# MIPI_To_HDMI.net
KiCad netlist of a schematic drawn in Altium Designer
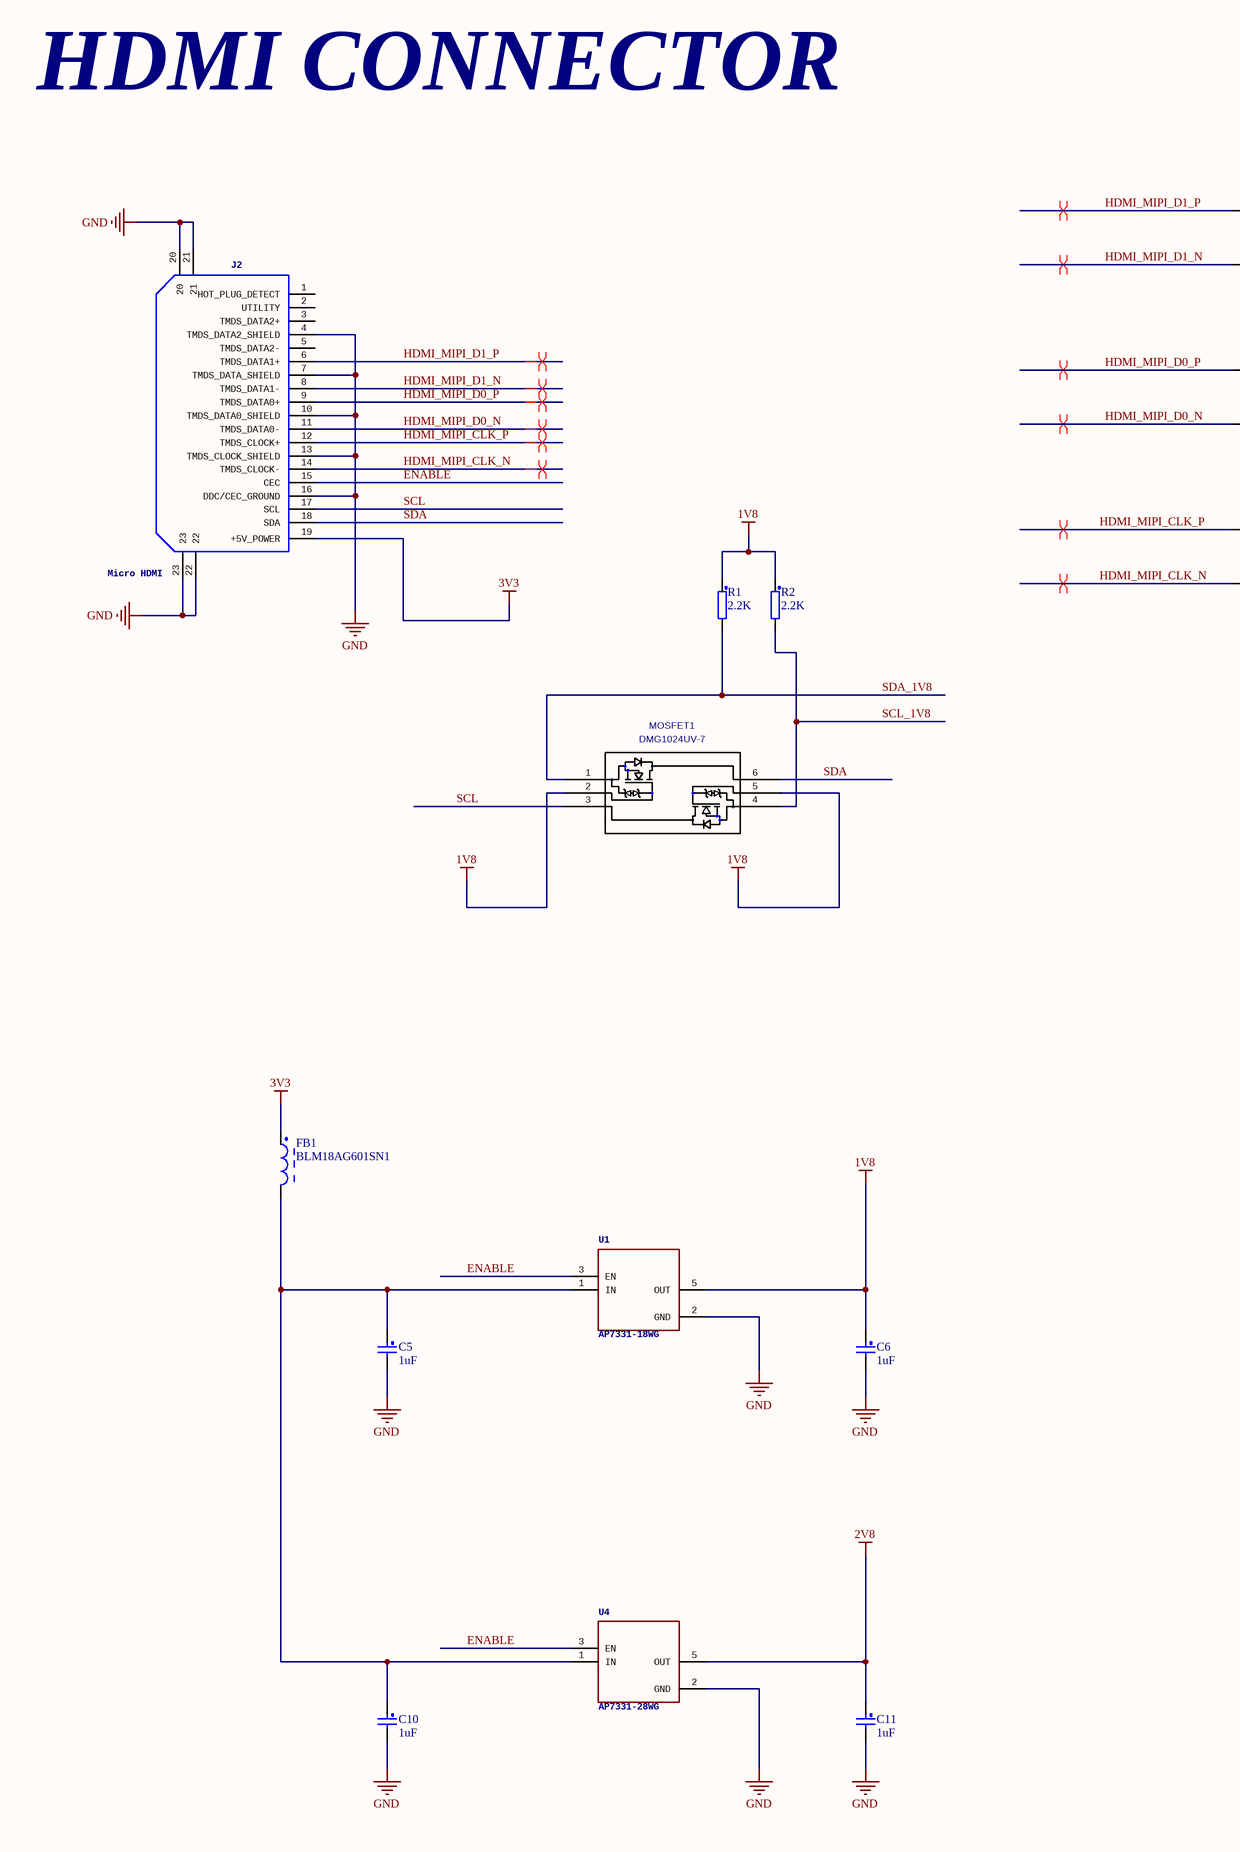
[diagram p0: MIPI_To_HDMI.SchDoc, left]
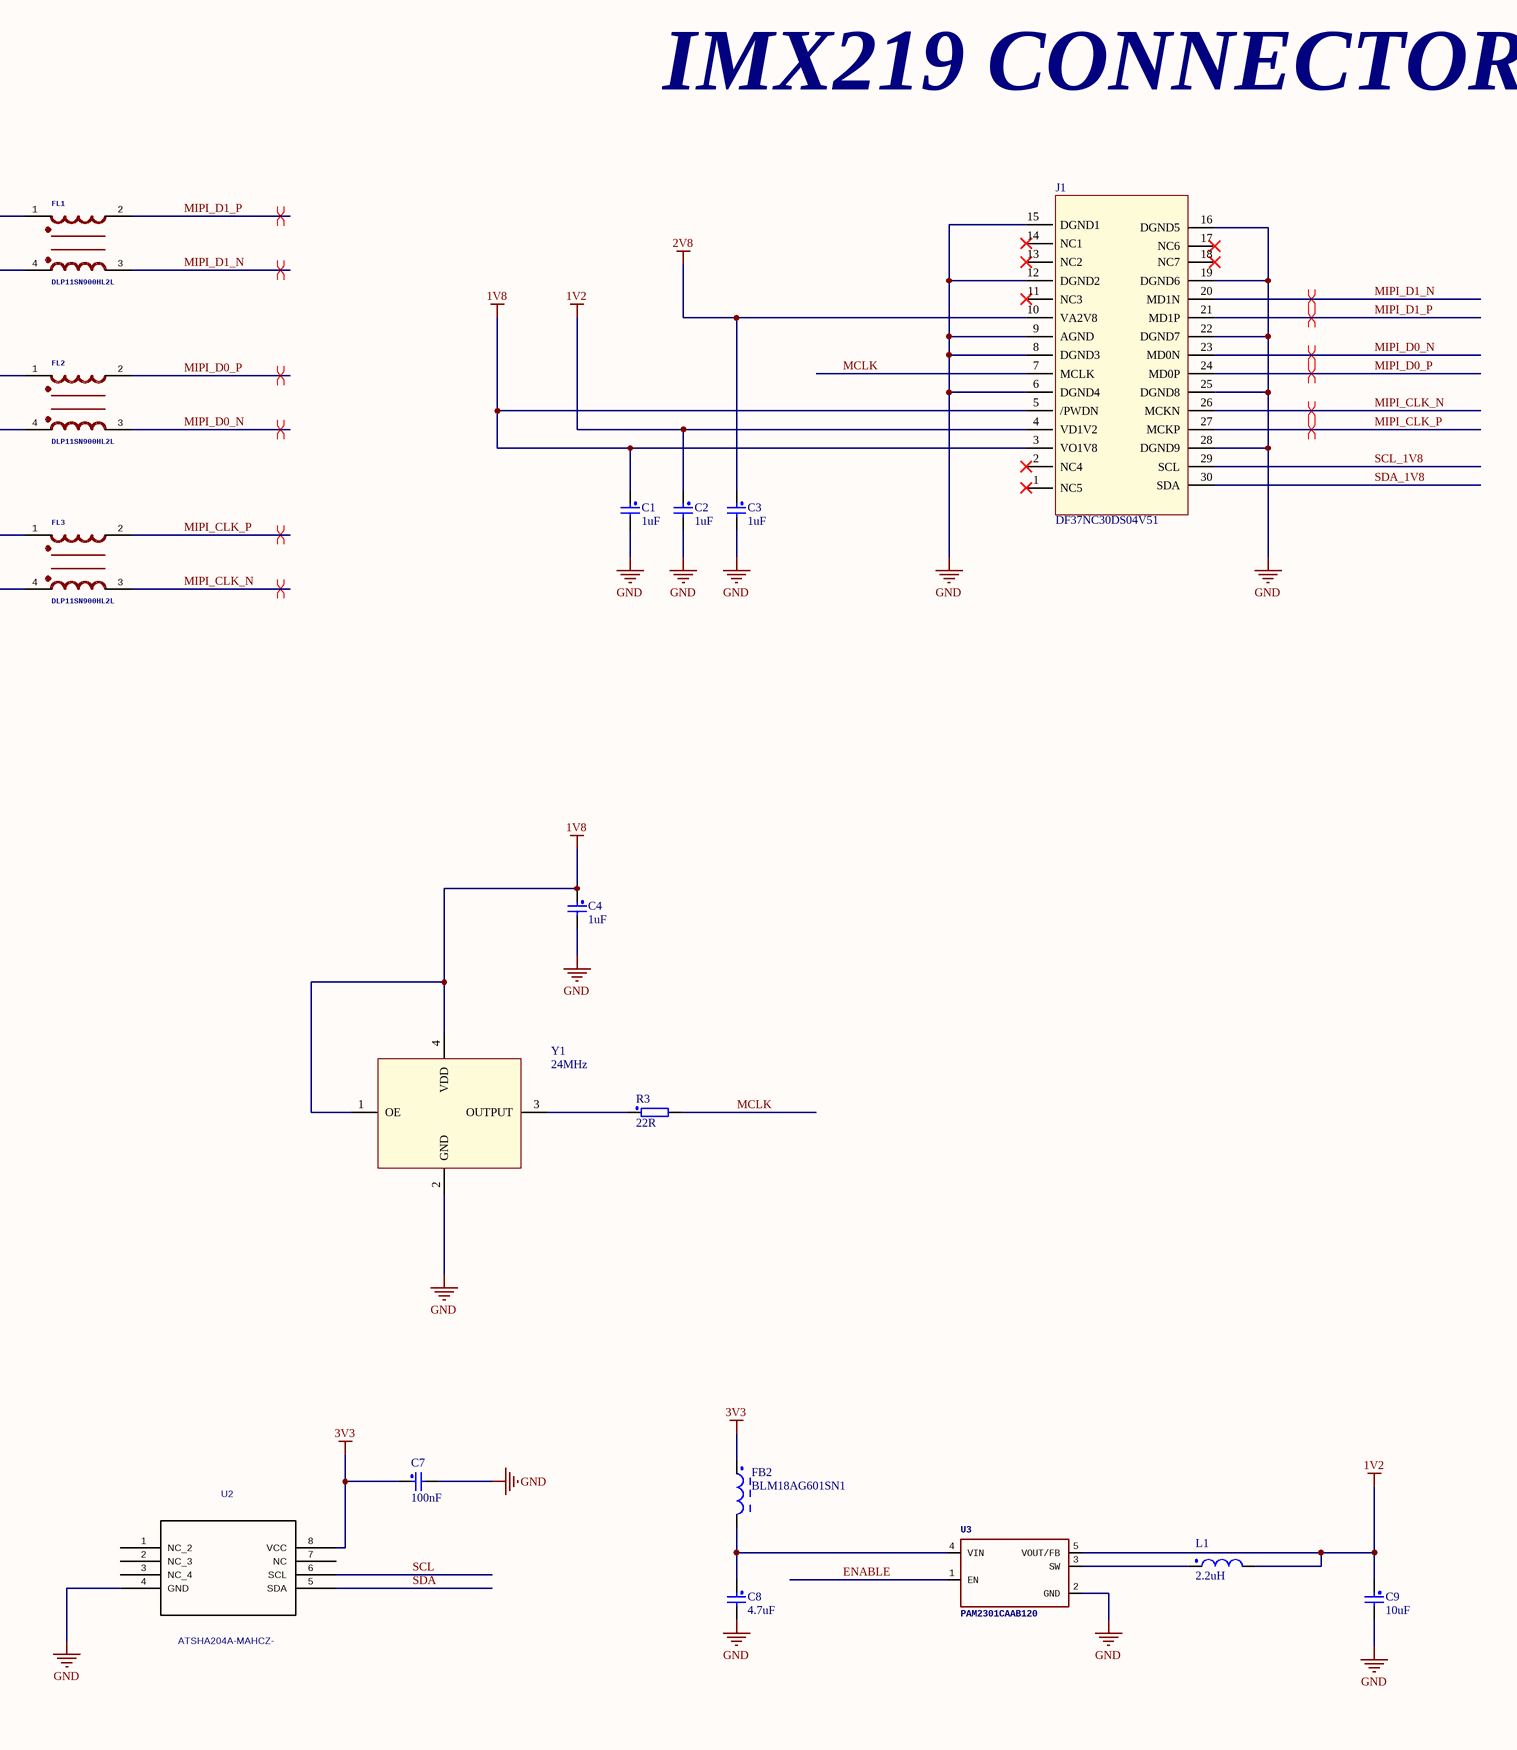
[diagram p1: MIPI_To_HDMI.SchDoc, right]

(export (version "E")
  (design (tool "Eeschema 10.0.6"))
  (components
    (comp (ref "C1")
      (value "1uF")
      (footprint "CAP-0402")
      (description "Capacitor")
      (libsource (lib "TASK-3DLIB") (part "CAP"))
    )
    (comp (ref "C2")
      (value "1uF")
      (footprint "CAP-0402")
      (description "Capacitor")
      (libsource (lib "TASK-3DLIB") (part "CAP"))
    )
    (comp (ref "C3")
      (value "1uF")
      (footprint "CAP-0402")
      (description "Capacitor")
      (libsource (lib "TASK-3DLIB") (part "CAP"))
    )
    (comp (ref "C4")
      (value "1uF")
      (footprint "CAP-0402")
      (description "Capacitor")
      (libsource (lib "TASK-3DLIB") (part "CAP"))
    )
    (comp (ref "C5")
      (value "1uF")
      (footprint "CAP-0402")
      (description "Capacitor")
      (libsource (lib "TASK-3DLIB") (part "CAP"))
    )
    (comp (ref "C6")
      (value "1uF")
      (footprint "CAP-0402")
      (description "Capacitor")
      (libsource (lib "TASK-3DLIB") (part "CAP"))
    )
    (comp (ref "C7")
      (value "100nF")
      (footprint "CAP-0402")
      (description "Capacitor")
      (libsource (lib "TASK-3DLIB") (part "CAP"))
    )
    (comp (ref "C8")
      (value "4.7uF")
      (footprint "CAP-0603")
      (description "Capacitor")
      (libsource (lib "TASK-3DLIB") (part "CAP"))
    )
    (comp (ref "C9")
      (value "10uF")
      (footprint "CAP-0805-S")
      (description "Capacitor")
      (libsource (lib "TASK-3DLIB") (part "CAP"))
    )
    (comp (ref "C10")
      (value "1uF")
      (footprint "CAP-0402")
      (description "Capacitor")
      (libsource (lib "TASK-3DLIB") (part "CAP"))
    )
    (comp (ref "C11")
      (value "1uF")
      (footprint "CAP-0402")
      (description "Capacitor")
      (libsource (lib "TASK-3DLIB") (part "CAP"))
    )
    (comp (ref "FB1")
      (value "BLM18AG601SN1")
      (footprint "FBD-0603-S")
      (description "Inductor")
      (libsource (lib "TASK-3DLIB") (part "INDUCTOR"))
    )
    (comp (ref "FB2")
      (value "BLM18AG601SN1")
      (footprint "FBD-0603-S")
      (description "Inductor")
      (libsource (lib "TASK-3DLIB") (part "INDUCTOR"))
    )
    (comp (ref "FL1")
      (value "DLP11SN900HL2L")
      (footprint "DLP11SN900HL2L")
      (fields (field (name "MF") "Murata") (field (name "DIGI-KEY_PART_NUMBER") "490-5143-1-ND"))
      (libsource (lib "TASK-3DLIB") (part "DLP11SN900HL2L"))
    )
    (comp (ref "FL2")
      (value "DLP11SN900HL2L")
      (footprint "DLP11SN900HL2L")
      (fields (field (name "MF") "Murata") (field (name "DIGI-KEY_PART_NUMBER") "490-5143-1-ND"))
      (libsource (lib "TASK-3DLIB") (part "DLP11SN900HL2L"))
    )
    (comp (ref "FL3")
      (value "DLP11SN900HL2L")
      (footprint "DLP11SN900HL2L")
      (fields (field (name "MF") "Murata") (field (name "DIGI-KEY_PART_NUMBER") "490-5143-1-ND"))
      (libsource (lib "TASK-3DLIB") (part "DLP11SN900HL2L"))
    )
    (comp (ref "J1")
      (value "DF37NC30DS04V51")
      (footprint "DF37NC30DS04V51")
      (libsource (lib "TASK-3DLIB") (part "DF37NC30DS04V51"))
    )
    (comp (ref "J2")
      (value "Micro HDMI")
      (footprint "HDMI-0467650301")
      (fields (field (name "MANUFACTURER_PART_NUMBER") "0467650301"))
      (libsource (lib "TASK-3DLIB") (part "HDMI-0467650301"))
    )
    (comp (ref "L1")
      (value "2.2uH")
      (footprint "IND-1008")
      (description "Inductor")
      (libsource (lib "TASK-3DLIB") (part "INDUCTOR"))
    )
    (comp (ref "MOSFET1")
      (value "DMG1024UV-7")
      (footprint "SOT-563_DIO")
      (fields (field (name "COPYRIGHT") "Copyright (C) 2018 Accelerated Designs. All rights reserved"))
      (libsource (lib "TASK-3DLIB") (part "DMG1024UV-7"))
    )
    (comp (ref "R1") (value "2.2K") (footprint "RES-0402") (libsource (lib "TASK-3DLIB") (part "RES")))
    (comp (ref "R2") (value "2.2K") (footprint "RES-0402") (libsource (lib "TASK-3DLIB") (part "RES")))
    (comp (ref "R3") (value "22R") (footprint "RES-0402") (libsource (lib "TASK-3DLIB") (part "RES")))
    (comp (ref "U1")
      (value "AP7331-18WG")
      (footprint "AP7331-sot-25")
      (fields
        (field (name "MP") "AP7331-18WG-7")
        (field (name "MF") "Diodes Inc.")
        (field (name "DIGI-KEY_PART_NUMBER") "AP7331-18WG-7DICT-ND")
      )
      (libsource (lib "TASK-3DLIB") (part "AP7331-xxWG-7"))
    )
    (comp (ref "U2")
      (value "ATSHA204A-MAHCZ-")
      (footprint "ATSHA204A")
      (fields
        (field (name "MANUFACTURER_PART_NUMBER") "ATSHA204A-MAHCZ-T")
        (field (name "COPYRIGHT") "Copyright (C) 2018 Accelerated Designs. All rights reserved")
      )
      (libsource (lib "TASK-3DLIB") (part "ATSHA204A-MAHCZ-"))
    )
    (comp (ref "U3")
      (value "PAM2301CAAB120")
      (footprint "PAM2301CAAB120")
      (fields (field (name "MF") "Diodes Inc.") (field (name "DIGI-KEY_PART_NUMBER") "PAM2301CAAB120DI-ND"))
      (libsource (lib "TASK-3DLIB") (part "PAM2301CAAB120"))
    )
    (comp (ref "U4")
      (value "AP7331-28WG")
      (footprint "AP7331-sot-25")
      (fields
        (field (name "MP") "AP7331-18WG-7")
        (field (name "MF") "Diodes Inc.")
        (field (name "DIGI-KEY_PART_NUMBER") "AP7331-18WG-7DICT-ND")
      )
      (libsource (lib "TASK-3DLIB") (part "AP7331-xxWG-7"))
    )
    (comp (ref "Y1") (value "24MHz") (footprint "3225-OSC") (libsource (lib "TASK-3DLIB") (part "OSC-3225")))
  )
  (nets
    (net (code "1") (name "/ENABLE") (class "Default")
      (node (ref "J2") (pin "15") (pinfunction "CEC_15") (pintype "passive"))
      (node (ref "U1") (pin "3") (pinfunction "EN_3") (pintype "passive"))
      (node (ref "U3") (pin "1") (pinfunction "EN_1") (pintype "passive"))
      (node (ref "U4") (pin "3") (pinfunction "EN_3") (pintype "passive"))
    )
    (net (code "2") (name "/HDMI_MIPI_CLK_N") (class "Default")
      (node (ref "FL3") (pin "4") (pinfunction "4_4") (pintype "passive"))
      (node (ref "J2") (pin "14") (pinfunction "TMDS_CLOCK-_14") (pintype "passive"))
    )
    (net (code "3") (name "/HDMI_MIPI_CLK_P") (class "Default")
      (node (ref "FL3") (pin "1") (pinfunction "1_1") (pintype "passive"))
      (node (ref "J2") (pin "12") (pinfunction "TMDS_CLOCK+_12") (pintype "passive"))
    )
    (net (code "4") (name "/HDMI_MIPI_D0_N") (class "Default")
      (node (ref "FL2") (pin "4") (pinfunction "4_4") (pintype "passive"))
      (node (ref "J2") (pin "11") (pinfunction "TMDS_DATA0-_11") (pintype "passive"))
    )
    (net (code "5") (name "/HDMI_MIPI_D0_P") (class "Default")
      (node (ref "FL2") (pin "1") (pinfunction "1_1") (pintype "passive"))
      (node (ref "J2") (pin "9") (pinfunction "TMDS_DATA0+_9") (pintype "passive"))
    )
    (net (code "6") (name "/HDMI_MIPI_D1_N") (class "Default")
      (node (ref "FL1") (pin "4") (pinfunction "4_4") (pintype "passive"))
      (node (ref "J2") (pin "8") (pinfunction "TMDS_DATA1-_8") (pintype "passive"))
    )
    (net (code "7") (name "/HDMI_MIPI_D1_P") (class "Default")
      (node (ref "FL1") (pin "1") (pinfunction "1_1") (pintype "passive"))
      (node (ref "J2") (pin "6") (pinfunction "TMDS_DATA1+_6") (pintype "passive"))
    )
    (net (code "8") (name "/MCLK") (class "Default")
      (node (ref "J1") (pin "7") (pinfunction "MCLK_7") (pintype "passive"))
      (node (ref "R3") (pin "2") (pintype "passive"))
    )
    (net (code "9") (name "/MIPI_CLK_N") (class "Default")
      (node (ref "FL3") (pin "3") (pinfunction "3_3") (pintype "passive"))
      (node (ref "J1") (pin "26") (pinfunction "MCKN_26") (pintype "passive"))
    )
    (net (code "10") (name "/MIPI_CLK_P") (class "Default")
      (node (ref "FL3") (pin "2") (pinfunction "2_2") (pintype "passive"))
      (node (ref "J1") (pin "27") (pinfunction "MCKP_27") (pintype "passive"))
    )
    (net (code "11") (name "/MIPI_D0_N") (class "Default")
      (node (ref "FL2") (pin "3") (pinfunction "3_3") (pintype "passive"))
      (node (ref "J1") (pin "23") (pinfunction "MD0N_23") (pintype "passive"))
    )
    (net (code "12") (name "/MIPI_D0_P") (class "Default")
      (node (ref "FL2") (pin "2") (pinfunction "2_2") (pintype "passive"))
      (node (ref "J1") (pin "24") (pinfunction "MD0P_24") (pintype "passive"))
    )
    (net (code "13") (name "/MIPI_D1_N") (class "Default")
      (node (ref "FL1") (pin "3") (pinfunction "3_3") (pintype "passive"))
      (node (ref "J1") (pin "20") (pinfunction "MD1N_20") (pintype "passive"))
    )
    (net (code "14") (name "/MIPI_D1_P") (class "Default")
      (node (ref "FL1") (pin "2") (pinfunction "2_2") (pintype "passive"))
      (node (ref "J1") (pin "21") (pinfunction "MD1P_21") (pintype "passive"))
    )
    (net (code "15") (name "/SCL") (class "Default")
      (node (ref "J2") (pin "17") (pinfunction "SCL_17") (pintype "passive"))
      (node (ref "MOSFET1") (pin "3") (pinfunction "D1_3") (pintype "passive"))
      (node (ref "U2") (pin "6") (pinfunction "SCL_6") (pintype "passive"))
    )
    (net (code "16") (name "/SCL_1V8") (class "Default")
      (node (ref "J1") (pin "29") (pinfunction "SCL_29") (pintype "passive"))
      (node (ref "MOSFET1") (pin "4") (pinfunction "S1_4") (pintype "passive"))
      (node (ref "R2") (pin "2") (pintype "passive"))
    )
    (net (code "17") (name "/SDA") (class "Default")
      (node (ref "J2") (pin "18") (pinfunction "SDA_18") (pintype "passive"))
      (node (ref "MOSFET1") (pin "6") (pinfunction "D2_6") (pintype "passive"))
      (node (ref "U2") (pin "5") (pinfunction "SDA_5") (pintype "passive"))
    )
    (net (code "18") (name "/SDA_1V8") (class "Default")
      (node (ref "J1") (pin "30") (pinfunction "SDA_30") (pintype "passive"))
      (node (ref "MOSFET1") (pin "1") (pinfunction "S2_1") (pintype "passive"))
      (node (ref "R1") (pin "2") (pintype "passive"))
    )
    (net (code "19") (name "1V2") (class "Default")
      (node (ref "C2") (pin "1") (pinfunction "1_1") (pintype "passive"))
      (node (ref "C9") (pin "1") (pinfunction "1_1") (pintype "passive"))
      (node (ref "J1") (pin "4") (pinfunction "VD1V2_4") (pintype "passive"))
      (node (ref "L1") (pin "2") (pinfunction "2_2") (pintype "passive"))
      (node (ref "U3") (pin "5") (pinfunction "VOUT/FB_5") (pintype "passive"))
    )
    (net (code "20") (name "1V8") (class "Default")
      (node (ref "C1") (pin "1") (pinfunction "1_1") (pintype "passive"))
      (node (ref "C4") (pin "1") (pinfunction "1_1") (pintype "passive"))
      (node (ref "C6") (pin "1") (pinfunction "1_1") (pintype "passive"))
      (node (ref "J1") (pin "3") (pinfunction "VO1V8_3") (pintype "passive"))
      (node (ref "J1") (pin "5") (pinfunction "/PWDN_5") (pintype "passive"))
      (node (ref "MOSFET1") (pin "2") (pinfunction "G2_2") (pintype "passive"))
      (node (ref "MOSFET1") (pin "5") (pinfunction "G1_5") (pintype "passive"))
      (node (ref "R1") (pin "1") (pintype "passive"))
      (node (ref "R2") (pin "1") (pintype "passive"))
      (node (ref "U1") (pin "5") (pinfunction "OUT_5") (pintype "passive"))
      (node (ref "Y1") (pin "1") (pinfunction "OE_1") (pintype "passive"))
      (node (ref "Y1") (pin "4") (pinfunction "VDD_4") (pintype "passive"))
    )
    (net (code "21") (name "2V8") (class "Default")
      (node (ref "C11") (pin "1") (pinfunction "1_1") (pintype "passive"))
      (node (ref "C3") (pin "1") (pinfunction "1_1") (pintype "passive"))
      (node (ref "J1") (pin "10") (pinfunction "VA2V8_10") (pintype "passive"))
      (node (ref "U4") (pin "5") (pinfunction "OUT_5") (pintype "passive"))
    )
    (net (code "22") (name "3V3") (class "Default")
      (node (ref "C7") (pin "1") (pinfunction "1_1") (pintype "passive"))
      (node (ref "FB1") (pin "1") (pinfunction "1_1") (pintype "passive"))
      (node (ref "FB2") (pin "1") (pinfunction "1_1") (pintype "passive"))
      (node (ref "J2") (pin "19") (pinfunction "+5V_POWER_19") (pintype "passive"))
      (node (ref "U2") (pin "8") (pinfunction "VCC_8") (pintype "power_in"))
    )
    (net (code "23") (name "GND") (class "Default")
      (node (ref "C1") (pin "2") (pinfunction "2_2") (pintype "passive"))
      (node (ref "C10") (pin "2") (pinfunction "2_2") (pintype "passive"))
      (node (ref "C11") (pin "2") (pinfunction "2_2") (pintype "passive"))
      (node (ref "C2") (pin "2") (pinfunction "2_2") (pintype "passive"))
      (node (ref "C3") (pin "2") (pinfunction "2_2") (pintype "passive"))
      (node (ref "C4") (pin "2") (pinfunction "2_2") (pintype "passive"))
      (node (ref "C5") (pin "2") (pinfunction "2_2") (pintype "passive"))
      (node (ref "C6") (pin "2") (pinfunction "2_2") (pintype "passive"))
      (node (ref "C7") (pin "2") (pinfunction "2_2") (pintype "passive"))
      (node (ref "C8") (pin "2") (pinfunction "2_2") (pintype "passive"))
      (node (ref "C9") (pin "2") (pinfunction "2_2") (pintype "passive"))
      (node (ref "J1") (pin "12") (pinfunction "DGND2_12") (pintype "passive"))
      (node (ref "J1") (pin "15") (pinfunction "DGND1_15") (pintype "passive"))
      (node (ref "J1") (pin "16") (pinfunction "DGND5_16") (pintype "passive"))
      (node (ref "J1") (pin "19") (pinfunction "DGND6_19") (pintype "passive"))
      (node (ref "J1") (pin "22") (pinfunction "DGND7_22") (pintype "passive"))
      (node (ref "J1") (pin "25") (pinfunction "DGND8_25") (pintype "passive"))
      (node (ref "J1") (pin "28") (pinfunction "DGND9_28") (pintype "passive"))
      (node (ref "J1") (pin "6") (pinfunction "DGND4_6") (pintype "passive"))
      (node (ref "J1") (pin "8") (pinfunction "DGND3_8") (pintype "passive"))
      (node (ref "J1") (pin "9") (pinfunction "AGND_9") (pintype "passive"))
      (node (ref "J2") (pin "10") (pinfunction "TMDS_DATA0_SHIELD_10") (pintype "passive"))
      (node (ref "J2") (pin "13") (pinfunction "TMDS_CLOCK_SHIELD_13") (pintype "passive"))
      (node (ref "J2") (pin "16") (pinfunction "DDC/CEC_GROUND_16") (pintype "passive"))
      (node (ref "J2") (pin "20") (pinfunction "20_20") (pintype "passive"))
      (node (ref "J2") (pin "21") (pinfunction "21_21") (pintype "passive"))
      (node (ref "J2") (pin "22") (pinfunction "22_22") (pintype "passive"))
      (node (ref "J2") (pin "23") (pinfunction "23_23") (pintype "passive"))
      (node (ref "J2") (pin "4") (pinfunction "TMDS_DATA2_SHIELD_4") (pintype "passive"))
      (node (ref "J2") (pin "7") (pinfunction "TMDS_DATA_SHIELD_7") (pintype "passive"))
      (node (ref "U1") (pin "2") (pinfunction "GND_2") (pintype "power_in"))
      (node (ref "U2") (pin "4") (pinfunction "GND_4") (pintype "power_in"))
      (node (ref "U3") (pin "2") (pinfunction "GND_2") (pintype "power_in"))
      (node (ref "U4") (pin "2") (pinfunction "GND_2") (pintype "power_in"))
      (node (ref "Y1") (pin "2") (pinfunction "GND_2") (pintype "passive"))
    )
    (net (code "24") (name "Net-(U1-IN)") (class "Default")
      (node (ref "C10") (pin "1") (pinfunction "1_1") (pintype "passive"))
      (node (ref "C5") (pin "1") (pinfunction "1_1") (pintype "passive"))
      (node (ref "FB1") (pin "2") (pinfunction "2_2") (pintype "passive"))
      (node (ref "U1") (pin "1") (pinfunction "IN_1") (pintype "passive"))
      (node (ref "U4") (pin "1") (pinfunction "IN_1") (pintype "passive"))
    )
    (net (code "25") (name "Net-(U3-SW)") (class "Default")
      (node (ref "L1") (pin "1") (pinfunction "1_1") (pintype "passive"))
      (node (ref "U3") (pin "3") (pinfunction "SW_3") (pintype "passive"))
    )
    (net (code "26") (name "Net-(U3-VIN)") (class "Default")
      (node (ref "C8") (pin "1") (pinfunction "1_1") (pintype "passive"))
      (node (ref "FB2") (pin "2") (pinfunction "2_2") (pintype "passive"))
      (node (ref "U3") (pin "4") (pinfunction "VIN_4") (pintype "passive"))
    )
    (net (code "27") (name "Net-(Y1-OUTPUT)") (class "Default")
      (node (ref "R3") (pin "1") (pintype "passive"))
      (node (ref "Y1") (pin "3") (pinfunction "OUTPUT_3") (pintype "passive"))
    )
    (net (code "28") (name "unconnected-(J1-NC1-Pad14)") (class "Default")
      (node (ref "J1") (pin "14") (pinfunction "NC1_14") (pintype "passive+no_connect"))
    )
    (net (code "29") (name "unconnected-(J1-NC2-Pad13)") (class "Default")
      (node (ref "J1") (pin "13") (pinfunction "NC2_13") (pintype "passive+no_connect"))
    )
    (net (code "30") (name "unconnected-(J1-NC3-Pad11)") (class "Default")
      (node (ref "J1") (pin "11") (pinfunction "NC3_11") (pintype "passive+no_connect"))
    )
    (net (code "31") (name "unconnected-(J1-NC4-Pad2)") (class "Default")
      (node (ref "J1") (pin "2") (pinfunction "NC4_2") (pintype "passive+no_connect"))
    )
    (net (code "32") (name "unconnected-(J1-NC5-Pad1)") (class "Default")
      (node (ref "J1") (pin "1") (pinfunction "NC5_1") (pintype "passive+no_connect"))
    )
    (net (code "33") (name "unconnected-(J1-NC6-Pad17)") (class "Default")
      (node (ref "J1") (pin "17") (pinfunction "NC6_17") (pintype "passive+no_connect"))
    )
    (net (code "34") (name "unconnected-(J1-NC7-Pad18)") (class "Default")
      (node (ref "J1") (pin "18") (pinfunction "NC7_18") (pintype "passive+no_connect"))
    )
    (net (code "35") (name "unconnected-(J2-HOT_PLUG_DETECT-Pad1)") (class "Default")
      (node (ref "J2") (pin "1") (pinfunction "HOT_PLUG_DETECT_1") (pintype "passive"))
    )
    (net (code "36") (name "unconnected-(J2-TMDS_DATA2+-Pad3)") (class "Default")
      (node (ref "J2") (pin "3") (pinfunction "TMDS_DATA2+_3") (pintype "passive"))
    )
    (net (code "37") (name "unconnected-(J2-TMDS_DATA2--Pad5)") (class "Default")
      (node (ref "J2") (pin "5") (pinfunction "TMDS_DATA2-_5") (pintype "passive"))
    )
    (net (code "38") (name "unconnected-(J2-UTILITY-Pad2)") (class "Default")
      (node (ref "J2") (pin "2") (pinfunction "UTILITY_2") (pintype "passive"))
    )
    (net (code "39") (name "unconnected-(U2-NC-Pad7)") (class "Default")
      (node (ref "U2") (pin "7") (pinfunction "NC_7") (pintype "passive"))
    )
    (net (code "40") (name "unconnected-(U2-NC_2-Pad1)") (class "Default")
      (node (ref "U2") (pin "1") (pinfunction "NC_2_1") (pintype "passive"))
    )
    (net (code "41") (name "unconnected-(U2-NC_3-Pad2)") (class "Default")
      (node (ref "U2") (pin "2") (pinfunction "NC_3_2") (pintype "passive"))
    )
    (net (code "42") (name "unconnected-(U2-NC_4-Pad3)") (class "Default")
      (node (ref "U2") (pin "3") (pinfunction "NC_4_3") (pintype "passive"))
    )
  )
)
